# Controller_1.net
KiCad netlist of a schematic drawn in Altium Designer
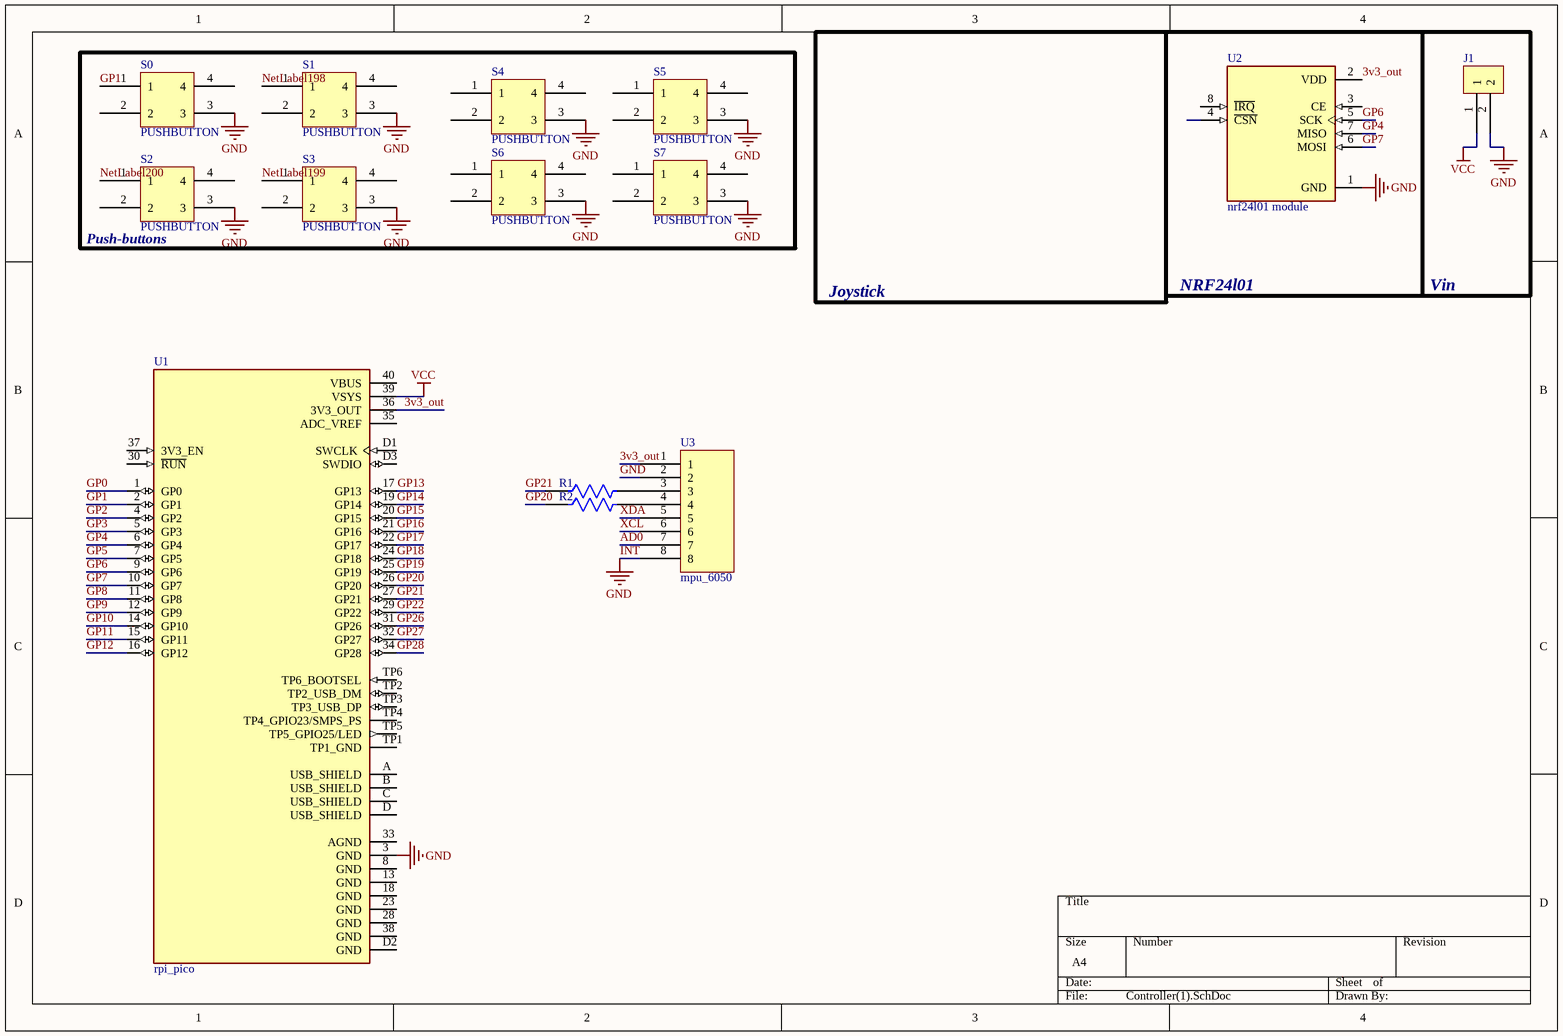
[diagram p0: Controller(1).SchDoc]

(export (version "E")
  (design (tool "Eeschema 10.0.6"))
  (components
    (comp (ref "J1")
      (value "2pin male header")
      (footprint "Controller:2pin")
      (libsource (lib "Controller") (part "2pin"))
    )
    (comp (ref "R1")
      (value "10k ohm resistor")
      (footprint "Controller:10k res")
      (libsource (lib "Controller") (part "10k res"))
    )
    (comp (ref "R2")
      (value "10k ohm resistor")
      (footprint "Controller:10k res")
      (libsource (lib "Controller") (part "10k res"))
    )
    (comp (ref "S0")
      (value "PUSHBUTTON")
      (footprint "Controller:pushbutton - duplicate")
      (libsource (lib "Controller") (part "PUSHBUTTON"))
    )
    (comp (ref "S1")
      (value "PUSHBUTTON")
      (footprint "Controller:pushbutton - duplicate")
      (libsource (lib "Controller") (part "PUSHBUTTON"))
    )
    (comp (ref "S2")
      (value "PUSHBUTTON")
      (footprint "Controller:pushbutton - duplicate")
      (libsource (lib "Controller") (part "PUSHBUTTON"))
    )
    (comp (ref "S3")
      (value "PUSHBUTTON")
      (footprint "Controller:pushbutton - duplicate")
      (libsource (lib "Controller") (part "PUSHBUTTON"))
    )
    (comp (ref "S4")
      (value "PUSHBUTTON")
      (footprint "Controller:pushbutton - duplicate")
      (libsource (lib "Controller") (part "PUSHBUTTON"))
    )
    (comp (ref "S5")
      (value "PUSHBUTTON")
      (footprint "Controller:pushbutton - duplicate")
      (libsource (lib "Controller") (part "PUSHBUTTON"))
    )
    (comp (ref "S6")
      (value "PUSHBUTTON")
      (footprint "Controller:pushbutton - duplicate")
      (libsource (lib "Controller") (part "PUSHBUTTON"))
    )
    (comp (ref "S7")
      (value "PUSHBUTTON")
      (footprint "Controller:pushbutton - duplicate")
      (libsource (lib "Controller") (part "PUSHBUTTON"))
    )
    (comp (ref "U1")
      (value "rpi_pico")
      (footprint "Controller:rpi_pico")
      (libsource (lib "Controller") (part "rpi_pico"))
    )
    (comp (ref "U2")
      (value "nrf24l01 module")
      (footprint "Controller:nrf24l01")
      (libsource (lib "Controller") (part "nrf24l01"))
    )
    (comp (ref "U3")
      (value "mpu_6050")
      (footprint "Controller:mpu_6050 - duplicate1")
      (libsource (lib "Controller") (part "mpu_6050"))
    )
  )
  (nets
    (net (code "1") (name "/3v3_out") (class "Default")
      (node (ref "U1") (pin "36") (pinfunction "3V3_OUT_36") (pintype "power_in"))
      (node (ref "U2") (pin "2") (pinfunction "VDD_2") (pintype "power_in"))
      (node (ref "U3") (pin "1") (pinfunction "1_1") (pintype "passive"))
    )
    (net (code "2") (name "/AD0") (class "Default")
      (node (ref "U3") (pin "7") (pinfunction "7_7") (pintype "passive"))
    )
    (net (code "3") (name "/GP0") (class "Default")
      (node (ref "U1") (pin "1") (pinfunction "GP0_1") (pintype "bidirectional"))
    )
    (net (code "4") (name "/GP1") (class "Default")
      (node (ref "S0") (pin "1") (pinfunction "1_1") (pintype "passive"))
      (node (ref "U1") (pin "2") (pinfunction "GP1_2") (pintype "bidirectional"))
    )
    (net (code "5") (name "/GP2") (class "Default")
      (node (ref "U1") (pin "4") (pinfunction "GP2_4") (pintype "bidirectional"))
    )
    (net (code "6") (name "/GP3") (class "Default")
      (node (ref "U1") (pin "5") (pinfunction "GP3_5") (pintype "bidirectional"))
    )
    (net (code "7") (name "/GP4") (class "Default")
      (node (ref "U1") (pin "6") (pinfunction "GP4_6") (pintype "bidirectional"))
      (node (ref "U2") (pin "7") (pinfunction "MISO_7") (pintype "input"))
    )
    (net (code "8") (name "/GP5") (class "Default")
      (node (ref "U1") (pin "7") (pinfunction "GP5_7") (pintype "bidirectional"))
    )
    (net (code "9") (name "/GP6") (class "Default")
      (node (ref "U1") (pin "9") (pinfunction "GP6_9") (pintype "bidirectional"))
      (node (ref "U2") (pin "5") (pinfunction "SCK_5") (pintype "input"))
    )
    (net (code "10") (name "/GP7") (class "Default")
      (node (ref "U1") (pin "10") (pinfunction "GP7_10") (pintype "bidirectional"))
      (node (ref "U2") (pin "6") (pinfunction "MOSI_6") (pintype "input"))
    )
    (net (code "11") (name "/GP8") (class "Default")
      (node (ref "U1") (pin "11") (pinfunction "GP8_11") (pintype "bidirectional"))
    )
    (net (code "12") (name "/GP9") (class "Default")
      (node (ref "U1") (pin "12") (pinfunction "GP9_12") (pintype "bidirectional"))
    )
    (net (code "13") (name "/GP10") (class "Default")
      (node (ref "U1") (pin "14") (pinfunction "GP10_14") (pintype "bidirectional"))
    )
    (net (code "14") (name "/GP11") (class "Default")
      (node (ref "U1") (pin "15") (pinfunction "GP11_15") (pintype "bidirectional"))
    )
    (net (code "15") (name "/GP12") (class "Default")
      (node (ref "U1") (pin "16") (pinfunction "GP12_16") (pintype "bidirectional"))
    )
    (net (code "16") (name "/GP13") (class "Default")
      (node (ref "U1") (pin "17") (pinfunction "GP13_17") (pintype "bidirectional"))
    )
    (net (code "17") (name "/GP14") (class "Default")
      (node (ref "U1") (pin "19") (pinfunction "GP14_19") (pintype "bidirectional"))
    )
    (net (code "18") (name "/GP15") (class "Default")
      (node (ref "U1") (pin "20") (pinfunction "GP15_20") (pintype "bidirectional"))
    )
    (net (code "19") (name "/GP16") (class "Default")
      (node (ref "U1") (pin "21") (pinfunction "GP16_21") (pintype "bidirectional"))
    )
    (net (code "20") (name "/GP17") (class "Default")
      (node (ref "U1") (pin "22") (pinfunction "GP17_22") (pintype "bidirectional"))
    )
    (net (code "21") (name "/GP18") (class "Default")
      (node (ref "U1") (pin "24") (pinfunction "GP18_24") (pintype "bidirectional"))
    )
    (net (code "22") (name "/GP19") (class "Default")
      (node (ref "U1") (pin "25") (pinfunction "GP19_25") (pintype "bidirectional"))
    )
    (net (code "23") (name "/GP20") (class "Default")
      (node (ref "R2") (pin "1") (pinfunction "1_1") (pintype "passive"))
      (node (ref "U1") (pin "26") (pinfunction "GP20_26") (pintype "bidirectional"))
    )
    (net (code "24") (name "/GP21") (class "Default")
      (node (ref "R1") (pin "1") (pinfunction "1_1") (pintype "passive"))
      (node (ref "U1") (pin "27") (pinfunction "GP21_27") (pintype "bidirectional"))
    )
    (net (code "25") (name "/GP22") (class "Default")
      (node (ref "U1") (pin "29") (pinfunction "GP22_29") (pintype "bidirectional"))
    )
    (net (code "26") (name "/GP26") (class "Default")
      (node (ref "U1") (pin "31") (pinfunction "GP26_31") (pintype "bidirectional"))
    )
    (net (code "27") (name "/GP27") (class "Default")
      (node (ref "U1") (pin "32") (pinfunction "GP27_32") (pintype "bidirectional"))
    )
    (net (code "28") (name "/GP28") (class "Default")
      (node (ref "U1") (pin "34") (pinfunction "GP28_34") (pintype "bidirectional"))
    )
    (net (code "29") (name "/NetLabel198") (class "Default")
      (node (ref "S1") (pin "1") (pinfunction "1_1") (pintype "passive"))
    )
    (net (code "30") (name "/NetLabel199") (class "Default")
      (node (ref "S3") (pin "1") (pinfunction "1_1") (pintype "passive"))
    )
    (net (code "31") (name "/NetLabel200") (class "Default")
      (node (ref "S2") (pin "1") (pinfunction "1_1") (pintype "passive"))
    )
    (net (code "32") (name "/XCL") (class "Default")
      (node (ref "U3") (pin "6") (pinfunction "6_6") (pintype "passive"))
    )
    (net (code "33") (name "/XDA") (class "Default")
      (node (ref "U3") (pin "5") (pinfunction "5_5") (pintype "passive"))
    )
    (net (code "34") (name "GND") (class "Default")
      (node (ref "J1") (pin "2") (pinfunction "2_2") (pintype "passive"))
      (node (ref "S0") (pin "3") (pinfunction "3_3") (pintype "passive"))
      (node (ref "S1") (pin "3") (pinfunction "3_3") (pintype "passive"))
      (node (ref "S2") (pin "3") (pinfunction "3_3") (pintype "passive"))
      (node (ref "S3") (pin "3") (pinfunction "3_3") (pintype "passive"))
      (node (ref "S4") (pin "3") (pinfunction "3_3") (pintype "passive"))
      (node (ref "S5") (pin "3") (pinfunction "3_3") (pintype "passive"))
      (node (ref "S6") (pin "3") (pinfunction "3_3") (pintype "passive"))
      (node (ref "S7") (pin "3") (pinfunction "3_3") (pintype "passive"))
      (node (ref "U1") (pin "3") (pinfunction "GND_3") (pintype "power_in"))
      (node (ref "U2") (pin "1") (pinfunction "GND_1") (pintype "power_in"))
      (node (ref "U3") (pin "2") (pinfunction "2_2") (pintype "passive"))
      (node (ref "U3") (pin "8") (pinfunction "8_8") (pintype "passive"))
    )
    (net (code "35") (name "Net-(R1-Pad2)") (class "Default")
      (node (ref "R1") (pin "2") (pinfunction "2_2") (pintype "passive"))
      (node (ref "U3") (pin "3") (pinfunction "3_3") (pintype "passive"))
    )
    (net (code "36") (name "Net-(R2-Pad2)") (class "Default")
      (node (ref "R2") (pin "2") (pinfunction "2_2") (pintype "passive"))
      (node (ref "U3") (pin "4") (pinfunction "4_4") (pintype "passive"))
    )
    (net (code "37") (name "VCC") (class "Default")
      (node (ref "J1") (pin "1") (pinfunction "1_1") (pintype "passive"))
      (node (ref "U1") (pin "39") (pinfunction "VSYS_39") (pintype "power_in"))
    )
    (net (code "38") (name "unconnected-(S0-Pad2)") (class "Default")
      (node (ref "S0") (pin "2") (pinfunction "2_2") (pintype "passive"))
    )
    (net (code "39") (name "unconnected-(S0-Pad4)") (class "Default")
      (node (ref "S0") (pin "4") (pinfunction "4_4") (pintype "passive"))
    )
    (net (code "40") (name "unconnected-(S1-Pad2)") (class "Default")
      (node (ref "S1") (pin "2") (pinfunction "2_2") (pintype "passive"))
    )
    (net (code "41") (name "unconnected-(S1-Pad4)") (class "Default")
      (node (ref "S1") (pin "4") (pinfunction "4_4") (pintype "passive"))
    )
    (net (code "42") (name "unconnected-(S2-Pad2)") (class "Default")
      (node (ref "S2") (pin "2") (pinfunction "2_2") (pintype "passive"))
    )
    (net (code "43") (name "unconnected-(S2-Pad4)") (class "Default")
      (node (ref "S2") (pin "4") (pinfunction "4_4") (pintype "passive"))
    )
    (net (code "44") (name "unconnected-(S3-Pad2)") (class "Default")
      (node (ref "S3") (pin "2") (pinfunction "2_2") (pintype "passive"))
    )
    (net (code "45") (name "unconnected-(S3-Pad4)") (class "Default")
      (node (ref "S3") (pin "4") (pinfunction "4_4") (pintype "passive"))
    )
    (net (code "46") (name "unconnected-(S4-Pad1)") (class "Default")
      (node (ref "S4") (pin "1") (pinfunction "1_1") (pintype "passive"))
    )
    (net (code "47") (name "unconnected-(S4-Pad2)") (class "Default")
      (node (ref "S4") (pin "2") (pinfunction "2_2") (pintype "passive"))
    )
    (net (code "48") (name "unconnected-(S4-Pad4)") (class "Default")
      (node (ref "S4") (pin "4") (pinfunction "4_4") (pintype "passive"))
    )
    (net (code "49") (name "unconnected-(S5-Pad1)") (class "Default")
      (node (ref "S5") (pin "1") (pinfunction "1_1") (pintype "passive"))
    )
    (net (code "50") (name "unconnected-(S5-Pad2)") (class "Default")
      (node (ref "S5") (pin "2") (pinfunction "2_2") (pintype "passive"))
    )
    (net (code "51") (name "unconnected-(S5-Pad4)") (class "Default")
      (node (ref "S5") (pin "4") (pinfunction "4_4") (pintype "passive"))
    )
    (net (code "52") (name "unconnected-(S6-Pad1)") (class "Default")
      (node (ref "S6") (pin "1") (pinfunction "1_1") (pintype "passive"))
    )
    (net (code "53") (name "unconnected-(S6-Pad2)") (class "Default")
      (node (ref "S6") (pin "2") (pinfunction "2_2") (pintype "passive"))
    )
    (net (code "54") (name "unconnected-(S6-Pad4)") (class "Default")
      (node (ref "S6") (pin "4") (pinfunction "4_4") (pintype "passive"))
    )
    (net (code "55") (name "unconnected-(S7-Pad1)") (class "Default")
      (node (ref "S7") (pin "1") (pinfunction "1_1") (pintype "passive"))
    )
    (net (code "56") (name "unconnected-(S7-Pad2)") (class "Default")
      (node (ref "S7") (pin "2") (pinfunction "2_2") (pintype "passive"))
    )
    (net (code "57") (name "unconnected-(S7-Pad4)") (class "Default")
      (node (ref "S7") (pin "4") (pinfunction "4_4") (pintype "passive"))
    )
    (net (code "58") (name "unconnected-(U1-3V3_EN-Pad37)") (class "Default")
      (node (ref "U1") (pin "37") (pinfunction "3V3_EN_37") (pintype "input"))
    )
    (net (code "59") (name "unconnected-(U1-ADC_VREF-Pad35)") (class "Default")
      (node (ref "U1") (pin "35") (pinfunction "ADC_VREF_35") (pintype "power_in"))
    )
    (net (code "60") (name "unconnected-(U1-AGND-Pad33)") (class "Default")
      (node (ref "U1") (pin "33") (pinfunction "AGND_33") (pintype "power_in"))
    )
    (net (code "61") (name "unconnected-(U1-GND-Pad8)") (class "Default")
      (node (ref "U1") (pin "8") (pinfunction "GND_8") (pintype "power_in"))
    )
    (net (code "62") (name "unconnected-(U1-GND-Pad13)") (class "Default")
      (node (ref "U1") (pin "13") (pinfunction "GND_13") (pintype "power_in"))
    )
    (net (code "63") (name "unconnected-(U1-GND-Pad18)") (class "Default")
      (node (ref "U1") (pin "18") (pinfunction "GND_18") (pintype "power_in"))
    )
    (net (code "64") (name "unconnected-(U1-GND-Pad23)") (class "Default")
      (node (ref "U1") (pin "23") (pinfunction "GND_23") (pintype "power_in"))
    )
    (net (code "65") (name "unconnected-(U1-GND-Pad28)") (class "Default")
      (node (ref "U1") (pin "28") (pinfunction "GND_28") (pintype "power_in"))
    )
    (net (code "66") (name "unconnected-(U1-GND-Pad38)") (class "Default")
      (node (ref "U1") (pin "38") (pinfunction "GND_38") (pintype "power_in"))
    )
    (net (code "67") (name "unconnected-(U1-GND-PadD2)") (class "Default")
      (node (ref "U1") (pin "D2") (pinfunction "GND_D2") (pintype "power_in"))
    )
    (net (code "68") (name "unconnected-(U1-SWCLK-PadD1)") (class "Default")
      (node (ref "U1") (pin "D1") (pinfunction "SWCLK_D1") (pintype "input"))
    )
    (net (code "69") (name "unconnected-(U1-SWDIO-PadD3)") (class "Default")
      (node (ref "U1") (pin "D3") (pinfunction "SWDIO_D3") (pintype "bidirectional"))
    )
    (net (code "70") (name "unconnected-(U1-TP1_GND-PadTP1)") (class "Default")
      (node (ref "U1") (pin "TP1") (pinfunction "TP1_GND_TP1") (pintype "power_in"))
    )
    (net (code "71") (name "unconnected-(U1-TP2_USB_DM-PadTP2)") (class "Default")
      (node (ref "U1") (pin "TP2") (pinfunction "TP2_USB_DM_TP2") (pintype "bidirectional"))
    )
    (net (code "72") (name "unconnected-(U1-TP3_USB_DP-PadTP3)") (class "Default")
      (node (ref "U1") (pin "TP3") (pinfunction "TP3_USB_DP_TP3") (pintype "bidirectional"))
    )
    (net (code "73") (name "unconnected-(U1-TP4_GPIO23{slash}SMPS_PS-PadTP4)") (class "Default")
      (node (ref "U1") (pin "TP4") (pinfunction "TP4_GPIO23/SMPS_PS_TP4") (pintype "passive"))
    )
    (net (code "74") (name "unconnected-(U1-TP5_GPIO25{slash}LED-PadTP5)") (class "Default")
      (node (ref "U1") (pin "TP5") (pinfunction "TP5_GPIO25/LED_TP5") (pintype "output"))
    )
    (net (code "75") (name "unconnected-(U1-TP6_BOOTSEL-PadTP6)") (class "Default")
      (node (ref "U1") (pin "TP6") (pinfunction "TP6_BOOTSEL_TP6") (pintype "input"))
    )
    (net (code "76") (name "unconnected-(U1-USB_SHIELD-PadA)") (class "Default")
      (node (ref "U1") (pin "A") (pinfunction "USB_SHIELD_A") (pintype "power_in"))
    )
    (net (code "77") (name "unconnected-(U1-USB_SHIELD-PadB)") (class "Default")
      (node (ref "U1") (pin "B") (pinfunction "USB_SHIELD_B") (pintype "power_in"))
    )
    (net (code "78") (name "unconnected-(U1-USB_SHIELD-PadC)") (class "Default")
      (node (ref "U1") (pin "C") (pinfunction "USB_SHIELD_C") (pintype "power_in"))
    )
    (net (code "79") (name "unconnected-(U1-USB_SHIELD-PadD)") (class "Default")
      (node (ref "U1") (pin "D") (pinfunction "USB_SHIELD_D") (pintype "power_in"))
    )
    (net (code "80") (name "unconnected-(U1-VBUS-Pad40)") (class "Default")
      (node (ref "U1") (pin "40") (pinfunction "VBUS_40") (pintype "power_in"))
    )
    (net (code "81") (name "unconnected-(U1-~{RUN}-Pad30)") (class "Default")
      (node (ref "U1") (pin "30") (pinfunction "~{RUN}_30") (pintype "input"))
    )
    (net (code "82") (name "unconnected-(U2-CE-Pad3)") (class "Default")
      (node (ref "U2") (pin "3") (pinfunction "CE_3") (pintype "input"))
    )
    (net (code "83") (name "unconnected-(U2-~{CSN}-Pad4)") (class "Default")
      (node (ref "U2") (pin "4") (pinfunction "~{CSN}_4") (pintype "input"))
    )
    (net (code "84") (name "unconnected-(U2-~{IRQ}-Pad8)") (class "Default")
      (node (ref "U2") (pin "8") (pinfunction "~{IRQ}_8") (pintype "input"))
    )
  )
)
